# 08_CoreBoard.net
KiCad netlist of a schematic drawn in Altium Designer
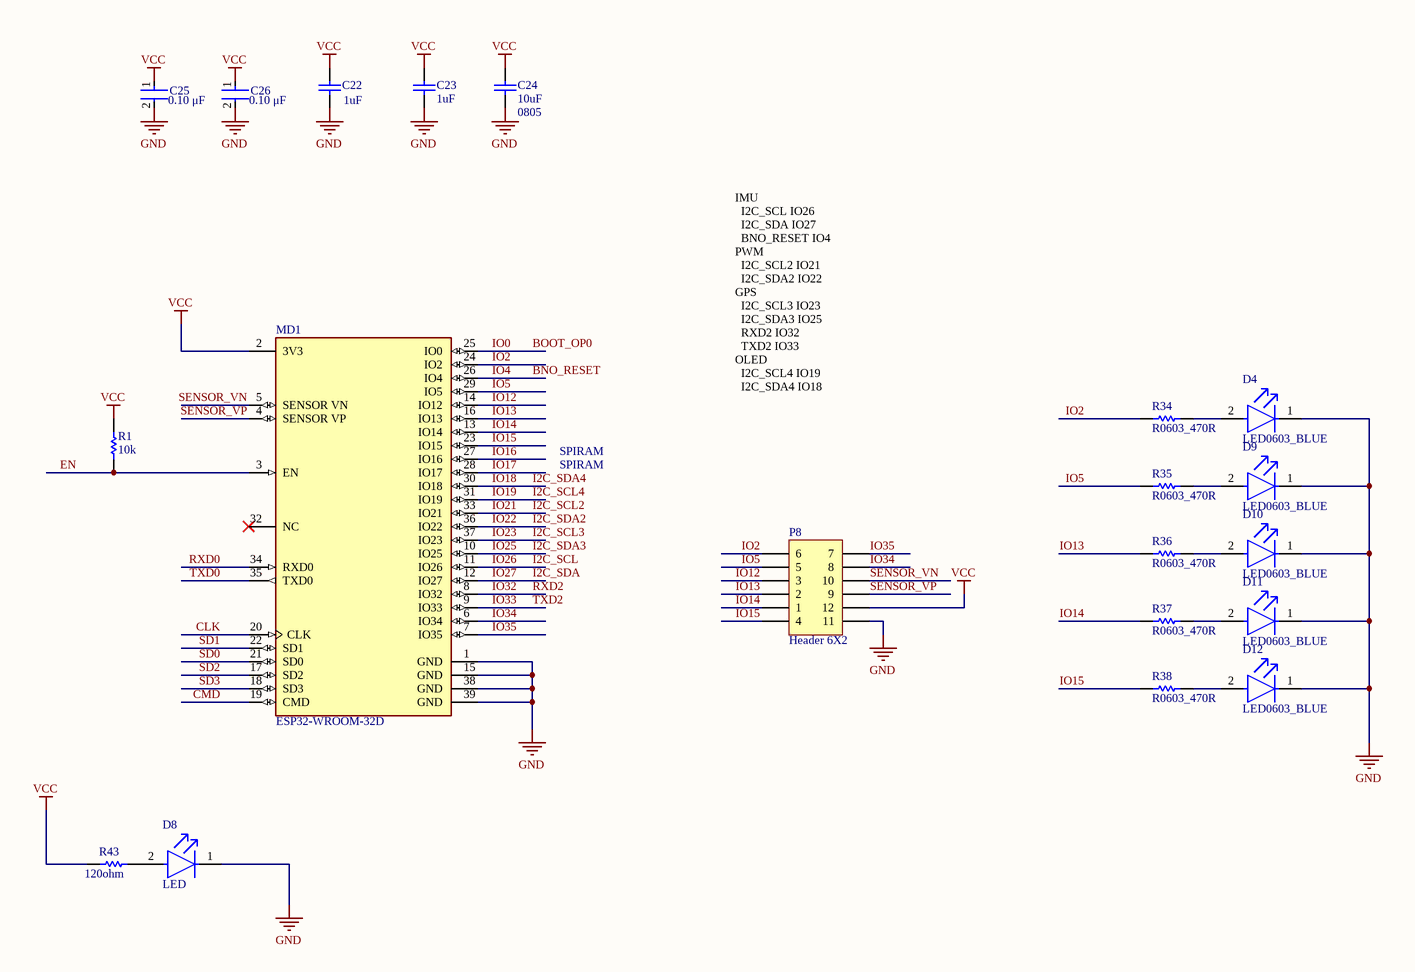
[diagram p0: 08_CoreBoard.SchDoc]

(export (version "E")
  (design (tool "Eeschema 10.0.6"))
  (components
    (comp (ref "C22")
      (value "1uF")
      (footprint "CAPC1608X87X35LL15T15")
      (fields
        (field (name "MANUFACTURER") "Kemet")
        (field (name "PART NUMBER") "C0603C101J1GACTU")
        (field (name "Comment") "C0603_1UF")
      )
      (libsource (lib "Altium Content Vault") (part "CAP"))
    )
    (comp (ref "C23")
      (value "1uF")
      (footprint "CAPC1608X87X35LL15T15")
      (fields
        (field (name "MANUFACTURER") "Kemet")
        (field (name "PART NUMBER") "C0603C101J1GACTU")
        (field (name "Comment") "C0603_1UF")
      )
      (libsource (lib "Altium Content Vault") (part "CAP"))
    )
    (comp (ref "C24")
      (value "10uF")
      (footprint "CAPC2013X135X50LL10T20")
      (fields
        (field (name "MANUFACTURER") "Murata")
        (field (name "PART NUMBER") "GRM21BR61C106KE15L")
        (field (name "PACKAGE") "0805")
        (field (name "Comment") "C0805_10UF")
      )
      (libsource (lib "Altium Content Vault") (part "CAP"))
    )
    (comp (ref "C25")
      (value "C0603_0.1UF")
      (footprint "FP-C0603C-CF-MFG")
      (description "CAP CER 0.1UF 16V X7R 0603")
      (fields
        (field (name "TOLERANCE") "0.2")
        (field (name "CAPACITANCE") "0.10 μF")
        (field (name "MANUFACTURER PART NUMBER") "C0603C104M4RAC7411")
      )
      (libsource (lib "Altium Content Vault") (part "b4654b650e69147ec39a6b967a45e02"))
    )
    (comp (ref "C26")
      (value "C0603_0.1UF")
      (footprint "FP-C0603C-CF-MFG")
      (description "CAP CER 0.1UF 16V X7R 0603")
      (fields
        (field (name "TOLERANCE") "0.2")
        (field (name "CAPACITANCE") "0.10 μF")
        (field (name "MANUFACTURER PART NUMBER") "C0603C104M4RAC7411")
      )
      (libsource (lib "Altium Content Vault") (part "b4654b650e69147ec39a6b967a45e02"))
    )
    (comp (ref "D4")
      (value "LED0603_BLUE")
      (footprint "FP-LTST-C191TBKT-MFG")
      (description "LED BLUE CLEAR CHIP SMD")
      (libsource (lib "Altium Content Vault") (part "8706943c75ba83719d021d2fdc84c58"))
    )
    (comp (ref "D8")
      (value "LED")
      (footprint "FP-LTST-C190GKT-MFG")
      (description "LED GREEN CLEAR CHIP SMD")
      (fields (field (name "VOLTAGE") "2V"))
      (libsource (lib "Altium Content Vault") (part "8706943c75ba83719d021d2fdc84c58"))
    )
    (comp (ref "D9")
      (value "LED0603_BLUE")
      (footprint "FP-LTST-C191TBKT-MFG")
      (description "LED BLUE CLEAR CHIP SMD")
      (libsource (lib "Altium Content Vault") (part "8706943c75ba83719d021d2fdc84c58"))
    )
    (comp (ref "D10")
      (value "LED0603_BLUE")
      (footprint "FP-LTST-C191TBKT-MFG")
      (description "LED BLUE CLEAR CHIP SMD")
      (libsource (lib "Altium Content Vault") (part "8706943c75ba83719d021d2fdc84c58"))
    )
    (comp (ref "D11")
      (value "LED0603_BLUE")
      (footprint "FP-LTST-C191TBKT-MFG")
      (description "LED BLUE CLEAR CHIP SMD")
      (libsource (lib "Altium Content Vault") (part "8706943c75ba83719d021d2fdc84c58"))
    )
    (comp (ref "D12")
      (value "LED0603_BLUE")
      (footprint "FP-LTST-C191TBKT-MFG")
      (description "LED BLUE CLEAR CHIP SMD")
      (libsource (lib "Altium Content Vault") (part "8706943c75ba83719d021d2fdc84c58"))
    )
    (comp (ref "MD1")
      (value "ESP32-WROOM-32D")
      (footprint "FP-ESP32-WROOM-32D-MFG")
      (description "WIFI MODULE 32MBITS SPI FLASH")
      (fields
        (field (name "OCTOPART") "https://octopart.com/esp32-wroom-32d-espressif+systems-91040050")
        (field (name "MANUFACTURER") "Espressif Systems")
      )
      (libsource (lib "Finger_module") (part "CMP-194065-000003-1"))
    )
    (comp (ref "P8")
      (value "Header 6X2")
      (footprint "HDR2X6")
      (description "Header, 6-Pin, Dual row")
      (fields (field (name "PUBLISHER") "Altium Limited"))
      (libsource (lib "Miscellaneous Connectors") (part "Header 6X2"))
    )
    (comp (ref "R1")
      (value "10k")
      (footprint "RESC1609X55X30LL15T15")
      (description "Chip Resistor, 10 KOhm, +/- 1%, 0.1 W, -55 to 155 degC, 0603 (1608 Metric), RoHS, Tape and Reel")
      (fields (field (name "TOLERANCE") "1%") (field (name "MANUFACTURER") "Panasonic"))
      (libsource (lib "Altium Content Vault") (part "RES-2"))
    )
    (comp (ref "R34")
      (value "R0603_470R")
      (footprint "RESC1608X55X30NL15T15")
      (fields (field (name "PART NUMBER") "ERJ-3GEYJ471V") (field (name "MANUFACTURER") "Panasonic"))
      (libsource (lib "Altium Content Vault") (part "RES"))
    )
    (comp (ref "R35")
      (value "R0603_470R")
      (footprint "RESC1608X55X30NL15T15")
      (fields (field (name "PART NUMBER") "ERJ-3GEYJ471V") (field (name "MANUFACTURER") "Panasonic"))
      (libsource (lib "Altium Content Vault") (part "RES"))
    )
    (comp (ref "R36")
      (value "R0603_470R")
      (footprint "RESC1608X55X30NL15T15")
      (fields (field (name "PART NUMBER") "ERJ-3GEYJ471V") (field (name "MANUFACTURER") "Panasonic"))
      (libsource (lib "Altium Content Vault") (part "RES"))
    )
    (comp (ref "R37")
      (value "R0603_470R")
      (footprint "RESC1608X55X30NL15T15")
      (fields (field (name "PART NUMBER") "ERJ-3GEYJ471V") (field (name "MANUFACTURER") "Panasonic"))
      (libsource (lib "Altium Content Vault") (part "RES"))
    )
    (comp (ref "R38")
      (value "R0603_470R")
      (footprint "RESC1608X55X30NL15T15")
      (fields (field (name "PART NUMBER") "ERJ-3GEYJ471V") (field (name "MANUFACTURER") "Panasonic"))
      (libsource (lib "Altium Content Vault") (part "RES"))
    )
    (comp (ref "R43")
      (value "120ohm")
      (footprint "RESC1608X55X30NL20T20")
      (fields
        (field (name "PART NUMBER") "ERA-3AEB121V")
        (field (name "MANUFACTURER") "Panasonic")
        (field (name "Comment") "R0603_120R")
      )
      (libsource (lib "Altium Content Vault") (part "RES"))
    )
  )
  (nets
    (net (code "1") (name "/BNO_RESET") (class "Default")
      (node (ref "MD1") (pin "26") (pinfunction "IO4_26") (pintype "bidirectional"))
    )
    (net (code "2") (name "/BOOT_OP0") (class "Default")
      (node (ref "MD1") (pin "25") (pinfunction "IO0_25") (pintype "bidirectional"))
    )
    (net (code "3") (name "/CLK") (class "Default")
      (node (ref "MD1") (pin "20") (pinfunction "CLK_20") (pintype "input"))
    )
    (net (code "4") (name "/CMD") (class "Default")
      (node (ref "MD1") (pin "19") (pinfunction "CMD_19") (pintype "bidirectional"))
    )
    (net (code "5") (name "/EN") (class "Default")
      (node (ref "MD1") (pin "3") (pinfunction "EN_3") (pintype "input"))
      (node (ref "R1") (pin "2") (pinfunction "2_2") (pintype "passive"))
    )
    (net (code "6") (name "/I2C_SCL") (class "Default")
      (node (ref "MD1") (pin "11") (pinfunction "IO26_11") (pintype "bidirectional"))
    )
    (net (code "7") (name "/I2C_SCL2") (class "Default")
      (node (ref "MD1") (pin "33") (pinfunction "IO21_33") (pintype "bidirectional"))
    )
    (net (code "8") (name "/I2C_SCL3") (class "Default")
      (node (ref "MD1") (pin "37") (pinfunction "IO23_37") (pintype "bidirectional"))
    )
    (net (code "9") (name "/I2C_SCL4") (class "Default")
      (node (ref "MD1") (pin "31") (pinfunction "IO19_31") (pintype "bidirectional"))
    )
    (net (code "10") (name "/I2C_SDA") (class "Default")
      (node (ref "MD1") (pin "12") (pinfunction "IO27_12") (pintype "bidirectional"))
    )
    (net (code "11") (name "/I2C_SDA2") (class "Default")
      (node (ref "MD1") (pin "36") (pinfunction "IO22_36") (pintype "bidirectional"))
    )
    (net (code "12") (name "/I2C_SDA3") (class "Default")
      (node (ref "MD1") (pin "10") (pinfunction "IO25_10") (pintype "bidirectional"))
    )
    (net (code "13") (name "/I2C_SDA4") (class "Default")
      (node (ref "MD1") (pin "30") (pinfunction "IO18_30") (pintype "bidirectional"))
    )
    (net (code "14") (name "/IO2") (class "Default")
      (node (ref "MD1") (pin "24") (pinfunction "IO2_24") (pintype "bidirectional"))
      (node (ref "P8") (pin "6") (pinfunction "6_6") (pintype "passive"))
      (node (ref "R34") (pin "1") (pinfunction "1_1") (pintype "passive"))
    )
    (net (code "15") (name "/IO5") (class "Default")
      (node (ref "MD1") (pin "29") (pinfunction "IO5_29") (pintype "bidirectional"))
      (node (ref "P8") (pin "5") (pinfunction "5_5") (pintype "passive"))
      (node (ref "R35") (pin "1") (pinfunction "1_1") (pintype "passive"))
    )
    (net (code "16") (name "/IO12") (class "Default")
      (node (ref "MD1") (pin "14") (pinfunction "IO12_14") (pintype "bidirectional"))
      (node (ref "P8") (pin "3") (pinfunction "3_3") (pintype "passive"))
    )
    (net (code "17") (name "/IO13") (class "Default")
      (node (ref "MD1") (pin "16") (pinfunction "IO13_16") (pintype "bidirectional"))
      (node (ref "P8") (pin "2") (pinfunction "2_2") (pintype "passive"))
      (node (ref "R36") (pin "1") (pinfunction "1_1") (pintype "passive"))
    )
    (net (code "18") (name "/IO14") (class "Default")
      (node (ref "MD1") (pin "13") (pinfunction "IO14_13") (pintype "bidirectional"))
      (node (ref "P8") (pin "1") (pinfunction "1_1") (pintype "passive"))
      (node (ref "R37") (pin "1") (pinfunction "1_1") (pintype "passive"))
    )
    (net (code "19") (name "/IO15") (class "Default")
      (node (ref "MD1") (pin "23") (pinfunction "IO15_23") (pintype "bidirectional"))
      (node (ref "P8") (pin "4") (pinfunction "4_4") (pintype "passive"))
      (node (ref "R38") (pin "1") (pinfunction "1_1") (pintype "passive"))
    )
    (net (code "20") (name "/IO16") (class "Default")
      (node (ref "MD1") (pin "27") (pinfunction "IO16_27") (pintype "bidirectional"))
    )
    (net (code "21") (name "/IO17") (class "Default")
      (node (ref "MD1") (pin "28") (pinfunction "IO17_28") (pintype "bidirectional"))
    )
    (net (code "22") (name "/IO32") (class "Default")
      (node (ref "MD1") (pin "8") (pinfunction "IO32_8") (pintype "bidirectional"))
    )
    (net (code "23") (name "/IO33") (class "Default")
      (node (ref "MD1") (pin "9") (pinfunction "IO33_9") (pintype "bidirectional"))
    )
    (net (code "24") (name "/IO34") (class "Default")
      (node (ref "MD1") (pin "6") (pinfunction "IO34_6") (pintype "bidirectional"))
      (node (ref "P8") (pin "8") (pinfunction "8_8") (pintype "passive"))
    )
    (net (code "25") (name "/IO35") (class "Default")
      (node (ref "MD1") (pin "7") (pinfunction "IO35_7") (pintype "bidirectional"))
      (node (ref "P8") (pin "7") (pinfunction "7_7") (pintype "passive"))
    )
    (net (code "26") (name "/RXD0") (class "Default")
      (node (ref "MD1") (pin "34") (pinfunction "RXD0_34") (pintype "input"))
    )
    (net (code "27") (name "/SD0") (class "Default")
      (node (ref "MD1") (pin "21") (pinfunction "SD0_21") (pintype "bidirectional"))
    )
    (net (code "28") (name "/SD1") (class "Default")
      (node (ref "MD1") (pin "22") (pinfunction "SD1_22") (pintype "bidirectional"))
    )
    (net (code "29") (name "/SD2") (class "Default")
      (node (ref "MD1") (pin "17") (pinfunction "SD2_17") (pintype "bidirectional"))
    )
    (net (code "30") (name "/SD3") (class "Default")
      (node (ref "MD1") (pin "18") (pinfunction "SD3_18") (pintype "bidirectional"))
    )
    (net (code "31") (name "/SENSOR_VN") (class "Default")
      (node (ref "MD1") (pin "5") (pinfunction "SENSOR_VN_5") (pintype "bidirectional"))
      (node (ref "P8") (pin "10") (pinfunction "10_10") (pintype "passive"))
    )
    (net (code "32") (name "/SENSOR_VP") (class "Default")
      (node (ref "MD1") (pin "4") (pinfunction "SENSOR_VP_4") (pintype "bidirectional"))
      (node (ref "P8") (pin "9") (pinfunction "9_9") (pintype "passive"))
    )
    (net (code "33") (name "/TXD0") (class "Default")
      (node (ref "MD1") (pin "35") (pinfunction "TXD0_35") (pintype "output"))
    )
    (net (code "34") (name "GND") (class "Default")
      (node (ref "C22") (pin "1") (pinfunction "1_1") (pintype "passive"))
      (node (ref "C23") (pin "1") (pinfunction "1_1") (pintype "passive"))
      (node (ref "C24") (pin "1") (pinfunction "1_1") (pintype "passive"))
      (node (ref "C25") (pin "2") (pinfunction "2_2") (pintype "passive"))
      (node (ref "C26") (pin "2") (pinfunction "2_2") (pintype "passive"))
      (node (ref "D10") (pin "1") (pinfunction "C_1") (pintype "passive"))
      (node (ref "D11") (pin "1") (pinfunction "C_1") (pintype "passive"))
      (node (ref "D12") (pin "1") (pinfunction "C_1") (pintype "passive"))
      (node (ref "D4") (pin "1") (pinfunction "C_1") (pintype "passive"))
      (node (ref "D8") (pin "1") (pinfunction "C_1") (pintype "passive"))
      (node (ref "D9") (pin "1") (pinfunction "C_1") (pintype "passive"))
      (node (ref "MD1") (pin "1") (pinfunction "GND_1") (pintype "power_in"))
      (node (ref "MD1") (pin "15") (pinfunction "GND_15") (pintype "power_in"))
      (node (ref "MD1") (pin "38") (pinfunction "GND_38") (pintype "power_in"))
      (node (ref "MD1") (pin "39") (pinfunction "GND_39") (pintype "power_in"))
      (node (ref "P8") (pin "11") (pinfunction "11_11") (pintype "passive"))
    )
    (net (code "35") (name "Net-(D4-A)") (class "Default")
      (node (ref "D4") (pin "2") (pinfunction "A_2") (pintype "passive"))
      (node (ref "R34") (pin "2") (pinfunction "2_2") (pintype "passive"))
    )
    (net (code "36") (name "Net-(D8-A)") (class "Default")
      (node (ref "D8") (pin "2") (pinfunction "A_2") (pintype "passive"))
      (node (ref "R43") (pin "2") (pinfunction "2_2") (pintype "passive"))
    )
    (net (code "37") (name "Net-(D9-A)") (class "Default")
      (node (ref "D9") (pin "2") (pinfunction "A_2") (pintype "passive"))
      (node (ref "R35") (pin "2") (pinfunction "2_2") (pintype "passive"))
    )
    (net (code "38") (name "Net-(D10-A)") (class "Default")
      (node (ref "D10") (pin "2") (pinfunction "A_2") (pintype "passive"))
      (node (ref "R36") (pin "2") (pinfunction "2_2") (pintype "passive"))
    )
    (net (code "39") (name "Net-(D11-A)") (class "Default")
      (node (ref "D11") (pin "2") (pinfunction "A_2") (pintype "passive"))
      (node (ref "R37") (pin "2") (pinfunction "2_2") (pintype "passive"))
    )
    (net (code "40") (name "Net-(D12-A)") (class "Default")
      (node (ref "D12") (pin "2") (pinfunction "A_2") (pintype "passive"))
      (node (ref "R38") (pin "2") (pinfunction "2_2") (pintype "passive"))
    )
    (net (code "41") (name "VCC") (class "Default")
      (node (ref "C22") (pin "2") (pinfunction "2_2") (pintype "passive"))
      (node (ref "C23") (pin "2") (pinfunction "2_2") (pintype "passive"))
      (node (ref "C24") (pin "2") (pinfunction "2_2") (pintype "passive"))
      (node (ref "C25") (pin "1") (pinfunction "1_1") (pintype "passive"))
      (node (ref "C26") (pin "1") (pinfunction "1_1") (pintype "passive"))
      (node (ref "MD1") (pin "2") (pinfunction "3V3_2") (pintype "power_in"))
      (node (ref "P8") (pin "12") (pinfunction "12_12") (pintype "passive"))
      (node (ref "R1") (pin "1") (pinfunction "1_1") (pintype "passive"))
      (node (ref "R43") (pin "1") (pinfunction "1_1") (pintype "passive"))
    )
    (net (code "42") (name "unconnected-(MD1-NC-Pad32)") (class "Default")
      (node (ref "MD1") (pin "32") (pinfunction "NC_32") (pintype "passive+no_connect"))
    )
  )
)
